# schemat.net
KiCad netlist of a schematic drawn in Altium Designer
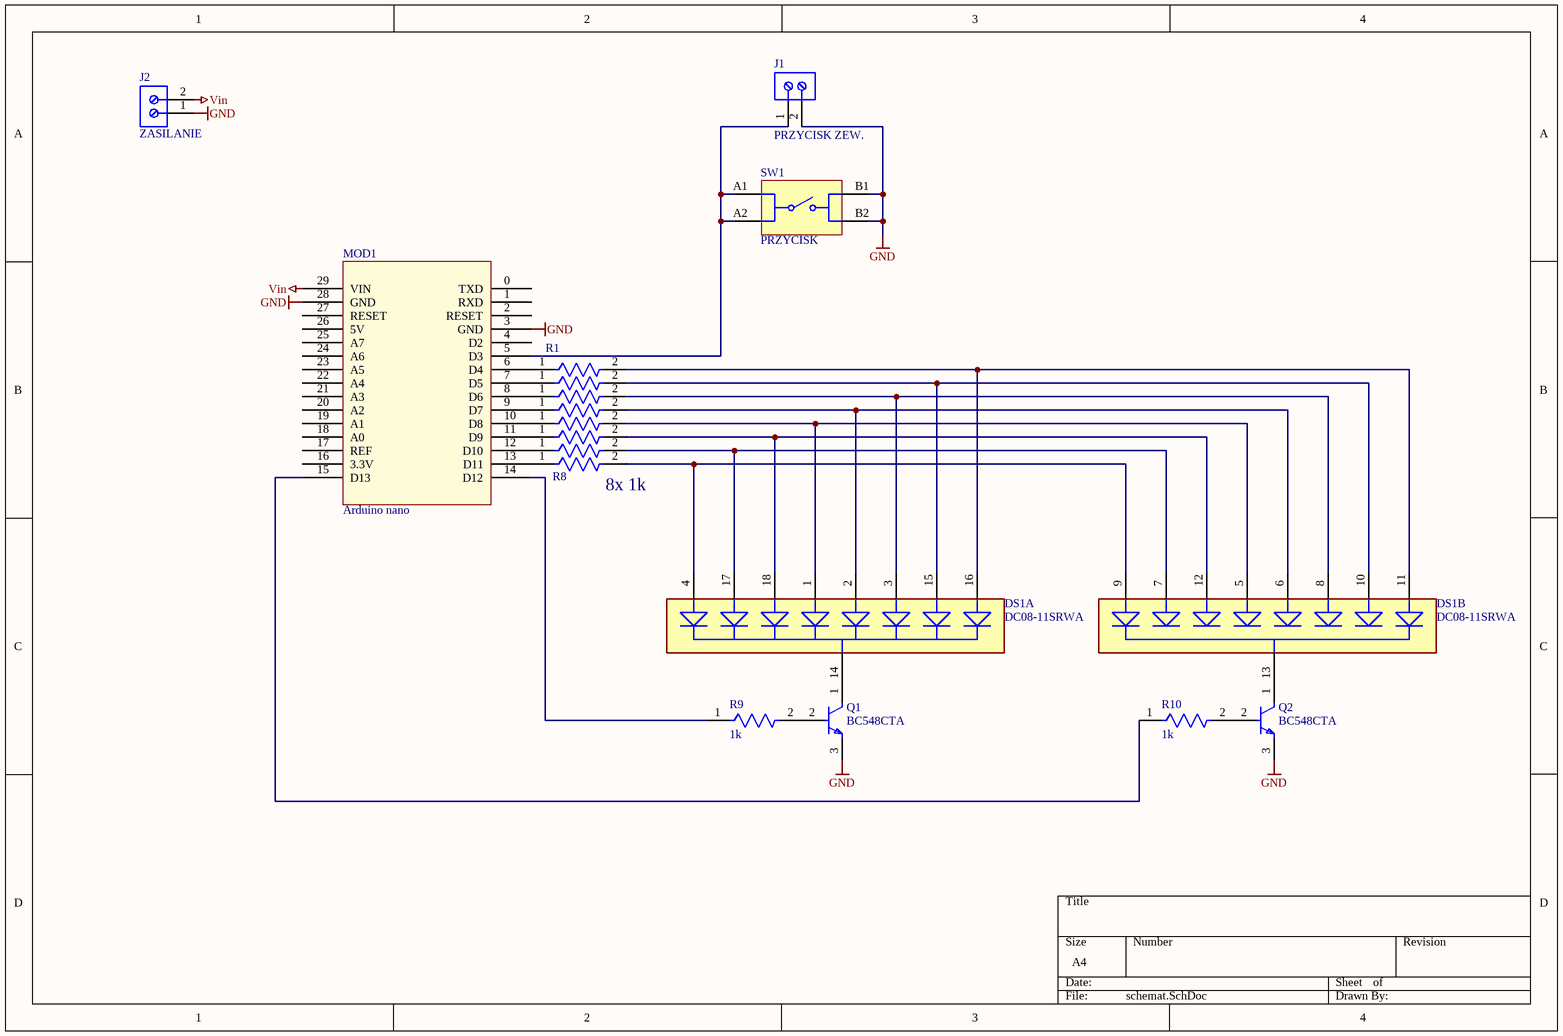
[diagram p0: schemat.SchDoc]

(export (version "E")
  (design (tool "Eeschema 10.0.6"))
  (components
    (comp (ref "DS1")
      (value "DC08-11SRWA")
      (footprint "FP-DC08-11SRWA-MFG")
      (description "DISPLAY 660NM RED 2DIG 0.8\" 7SEG")
      (fields
        (field (name "MANUFACTURER") "Kingbright")
        (field (name "OCTOPART") "https://octopart.com/dc08-11srwa-kingbright-55457135")
      )
      (libsource (lib "Altium Content Vault") (part "c040866fd5d19d735211b9114a29ce2"))
    )
    (comp (ref "J1")
      (value "PRZYCISK ZEW.")
      (footprint "691102710002")
      (fields (field (name "VOLTAGE") "300V"))
      (libsource (lib "Altium Content Vault") (part "TBL - 1R - 02P - Screw"))
    )
    (comp (ref "J2")
      (value "ZASILANIE")
      (footprint "691102710002")
      (fields (field (name "VOLTAGE") "300V"))
      (libsource (lib "Altium Content Vault") (part "TBL - 1R - 02P - Screw"))
    )
    (comp (ref "MOD1")
      (value "Arduino nano")
      (footprint "Arduino nano")
      (libsource (lib "schematic") (part "Arduino_nano"))
    )
    (comp (ref "Q1")
      (value "BC548CTA")
      (footprint "FP-135AR-MFG")
      (description "BC548CTA Small Signal Bipolar Transistor, 0.1A I(C), 30V V(BR)CEO, 1-Element, NPN, Silicon, TO-92")
      (libsource (lib "Altium Content Vault") (part "ddb5dc480c9317d3b8a15cf6cf16fd3"))
    )
    (comp (ref "Q2")
      (value "BC548CTA")
      (footprint "FP-135AR-MFG")
      (description "BC548CTA Small Signal Bipolar Transistor, 0.1A I(C), 30V V(BR)CEO, 1-Element, NPN, Silicon, TO-92")
      (libsource (lib "Altium Content Vault") (part "ddb5dc480c9317d3b8a15cf6cf16fd3"))
    )
    (comp (ref "R1")
      (value "1k")
      (footprint "FP-CF18-MFG")
      (description "RES 10K OHM 1/8W 5% CF AXIAL")
      (fields
        (field (name "MANUFACTURER PART NUMBER") "CF18JT10K0")
        (field (name "MANUFACTURER") "Stackpole Electronics")
      )
      (libsource (lib "Altium Content Vault") (part "1029c3af85768c4190bb7ad29bc67b5"))
    )
    (comp (ref "R2")
      (value "1k")
      (footprint "FP-CF18-MFG")
      (description "RES 10K OHM 1/8W 5% CF AXIAL")
      (fields
        (field (name "MANUFACTURER PART NUMBER") "CF18JT10K0")
        (field (name "MANUFACTURER") "Stackpole Electronics")
      )
      (libsource (lib "Altium Content Vault") (part "1029c3af85768c4190bb7ad29bc67b5"))
    )
    (comp (ref "R3")
      (value "1k")
      (footprint "FP-CF18-MFG")
      (description "RES 10K OHM 1/8W 5% CF AXIAL")
      (fields
        (field (name "MANUFACTURER PART NUMBER") "CF18JT10K0")
        (field (name "MANUFACTURER") "Stackpole Electronics")
      )
      (libsource (lib "Altium Content Vault") (part "1029c3af85768c4190bb7ad29bc67b5"))
    )
    (comp (ref "R4")
      (value "1k")
      (footprint "FP-CF18-MFG")
      (description "RES 10K OHM 1/8W 5% CF AXIAL")
      (fields
        (field (name "MANUFACTURER PART NUMBER") "CF18JT10K0")
        (field (name "MANUFACTURER") "Stackpole Electronics")
      )
      (libsource (lib "Altium Content Vault") (part "1029c3af85768c4190bb7ad29bc67b5"))
    )
    (comp (ref "R5")
      (value "1k")
      (footprint "FP-CF18-MFG")
      (description "RES 10K OHM 1/8W 5% CF AXIAL")
      (fields
        (field (name "MANUFACTURER PART NUMBER") "CF18JT10K0")
        (field (name "MANUFACTURER") "Stackpole Electronics")
      )
      (libsource (lib "Altium Content Vault") (part "1029c3af85768c4190bb7ad29bc67b5"))
    )
    (comp (ref "R6")
      (value "1k")
      (footprint "FP-CF18-MFG")
      (description "RES 10K OHM 1/8W 5% CF AXIAL")
      (fields
        (field (name "MANUFACTURER PART NUMBER") "CF18JT10K0")
        (field (name "MANUFACTURER") "Stackpole Electronics")
      )
      (libsource (lib "Altium Content Vault") (part "1029c3af85768c4190bb7ad29bc67b5"))
    )
    (comp (ref "R7")
      (value "1k")
      (footprint "FP-CF18-MFG")
      (description "RES 10K OHM 1/8W 5% CF AXIAL")
      (fields
        (field (name "MANUFACTURER PART NUMBER") "CF18JT10K0")
        (field (name "MANUFACTURER") "Stackpole Electronics")
      )
      (libsource (lib "Altium Content Vault") (part "1029c3af85768c4190bb7ad29bc67b5"))
    )
    (comp (ref "R8")
      (value "1k")
      (footprint "FP-CF18-MFG")
      (description "RES 10K OHM 1/8W 5% CF AXIAL")
      (fields
        (field (name "MANUFACTURER PART NUMBER") "CF18JT10K0")
        (field (name "MANUFACTURER") "Stackpole Electronics")
      )
      (libsource (lib "Altium Content Vault") (part "1029c3af85768c4190bb7ad29bc67b5"))
    )
    (comp (ref "R9")
      (value "1k")
      (footprint "FP-CF18-MFG")
      (description "RES 10K OHM 1/8W 5% CF AXIAL")
      (fields
        (field (name "MANUFACTURER PART NUMBER") "CF18JT10K0")
        (field (name "MANUFACTURER") "Stackpole Electronics")
      )
      (libsource (lib "Altium Content Vault") (part "1029c3af85768c4190bb7ad29bc67b5"))
    )
    (comp (ref "R10")
      (value "1k")
      (footprint "FP-CF18-MFG")
      (description "RES 10K OHM 1/8W 5% CF AXIAL")
      (fields
        (field (name "MANUFACTURER PART NUMBER") "CF18JT10K0")
        (field (name "MANUFACTURER") "Stackpole Electronics")
      )
      (libsource (lib "Altium Content Vault") (part "1029c3af85768c4190bb7ad29bc67b5"))
    )
    (comp (ref "SW1")
      (value "PRZYCISK")
      (footprint "4304x60437x6")
      (libsource (lib "Altium Content Vault") (part "SPST-NO_4P"))
    )
  )
  (nets
    (net (code "1") (name "GND") (class "Default")
      (node (ref "J1") (pin "2") (pinfunction "2_2") (pintype "passive"))
      (node (ref "J2") (pin "1") (pinfunction "1_1") (pintype "passive"))
      (node (ref "MOD1") (pin "28") (pinfunction "GND_28") (pintype "passive"))
      (node (ref "MOD1") (pin "3") (pinfunction "GND_3") (pintype "passive"))
      (node (ref "Q1") (pin "3") (pinfunction "E_3") (pintype "passive"))
      (node (ref "Q2") (pin "3") (pinfunction "E_3") (pintype "passive"))
      (node (ref "SW1") (pin "B1") (pinfunction "B1_B1") (pintype "passive"))
      (node (ref "SW1") (pin "B2") (pinfunction "B2_B2") (pintype "passive"))
    )
    (net (code "2") (name "Net-(DS1A-Anode_Dp1_Dig1)") (class "Default")
      (node (ref "DS1") (pin "4") (pinfunction "Anode_Dp1_Dig1_4") (pintype "passive"))
      (node (ref "DS1") (pin "9") (pinfunction "Anode_Dp2_Dig2_9") (pintype "passive"))
      (node (ref "R8") (pin "2") (pinfunction "2_2") (pintype "passive"))
    )
    (net (code "3") (name "Net-(DS1A-Anode_a_Dig1)") (class "Default")
      (node (ref "DS1") (pin "11") (pinfunction "Anode_a_Dig2_11") (pintype "passive"))
      (node (ref "DS1") (pin "16") (pinfunction "Anode_a_Dig1_16") (pintype "passive"))
      (node (ref "R1") (pin "2") (pinfunction "2_2") (pintype "passive"))
    )
    (net (code "4") (name "Net-(DS1A-Anode_b_Dig1)") (class "Default")
      (node (ref "DS1") (pin "10") (pinfunction "Anode_b_Dig2_10") (pintype "passive"))
      (node (ref "DS1") (pin "15") (pinfunction "Anode_b_Dig1_15") (pintype "passive"))
      (node (ref "R2") (pin "2") (pinfunction "2_2") (pintype "passive"))
    )
    (net (code "5") (name "Net-(DS1A-Anode_c_Dig1)") (class "Default")
      (node (ref "DS1") (pin "3") (pinfunction "Anode_c_Dig1_3") (pintype "passive"))
      (node (ref "DS1") (pin "8") (pinfunction "Anode_c_Dig2_8") (pintype "passive"))
      (node (ref "R3") (pin "2") (pinfunction "2_2") (pintype "passive"))
    )
    (net (code "6") (name "Net-(DS1A-Anode_d_Dig1)") (class "Default")
      (node (ref "DS1") (pin "2") (pinfunction "Anode_d_Dig1_2") (pintype "passive"))
      (node (ref "DS1") (pin "6") (pinfunction "Anode_d_Dig2_6") (pintype "passive"))
      (node (ref "R4") (pin "2") (pinfunction "2_2") (pintype "passive"))
    )
    (net (code "7") (name "Net-(DS1A-Anode_e_Dig1)") (class "Default")
      (node (ref "DS1") (pin "1") (pinfunction "Anode_e_Dig1_1") (pintype "passive"))
      (node (ref "DS1") (pin "5") (pinfunction "Anode_e_Dig2_5") (pintype "passive"))
      (node (ref "R5") (pin "2") (pinfunction "2_2") (pintype "passive"))
    )
    (net (code "8") (name "Net-(DS1A-Anode_f_Dig1)") (class "Default")
      (node (ref "DS1") (pin "12") (pinfunction "Anode_f_Dig2_12") (pintype "passive"))
      (node (ref "DS1") (pin "18") (pinfunction "Anode_f_Dig1_18") (pintype "passive"))
      (node (ref "R6") (pin "2") (pinfunction "2_2") (pintype "passive"))
    )
    (net (code "9") (name "Net-(DS1A-Anode_g_Dig1)") (class "Default")
      (node (ref "DS1") (pin "17") (pinfunction "Anode_g_Dig1_17") (pintype "passive"))
      (node (ref "DS1") (pin "7") (pinfunction "Anode_g_Dig2_7") (pintype "passive"))
      (node (ref "R7") (pin "2") (pinfunction "2_2") (pintype "passive"))
    )
    (net (code "10") (name "Net-(DS1A-Common_Cathode_Dig1)") (class "Default")
      (node (ref "DS1") (pin "14") (pinfunction "Common_Cathode_Dig1_14") (pintype "passive"))
      (node (ref "Q1") (pin "1") (pinfunction "C_1") (pintype "passive"))
    )
    (net (code "11") (name "Net-(DS1B-Common_Cathode_Dig2)") (class "Default")
      (node (ref "DS1") (pin "13") (pinfunction "Common_Cathode_Dig2_13") (pintype "passive"))
      (node (ref "Q2") (pin "1") (pinfunction "C_1") (pintype "passive"))
    )
    (net (code "12") (name "Net-(MOD1-D3)") (class "Default")
      (node (ref "J1") (pin "1") (pinfunction "1_1") (pintype "passive"))
      (node (ref "MOD1") (pin "5") (pinfunction "D3_5") (pintype "passive"))
      (node (ref "SW1") (pin "A1") (pinfunction "A1_A1") (pintype "passive"))
      (node (ref "SW1") (pin "A2") (pinfunction "A2_A2") (pintype "passive"))
    )
    (net (code "13") (name "Net-(MOD1-D4)") (class "Default")
      (node (ref "MOD1") (pin "6") (pinfunction "D4_6") (pintype "passive"))
      (node (ref "R1") (pin "1") (pinfunction "1_1") (pintype "passive"))
    )
    (net (code "14") (name "Net-(MOD1-D5)") (class "Default")
      (node (ref "MOD1") (pin "7") (pinfunction "D5_7") (pintype "passive"))
      (node (ref "R2") (pin "1") (pinfunction "1_1") (pintype "passive"))
    )
    (net (code "15") (name "Net-(MOD1-D6)") (class "Default")
      (node (ref "MOD1") (pin "8") (pinfunction "D6_8") (pintype "passive"))
      (node (ref "R3") (pin "1") (pinfunction "1_1") (pintype "passive"))
    )
    (net (code "16") (name "Net-(MOD1-D7)") (class "Default")
      (node (ref "MOD1") (pin "9") (pinfunction "D7_9") (pintype "passive"))
      (node (ref "R4") (pin "1") (pinfunction "1_1") (pintype "passive"))
    )
    (net (code "17") (name "Net-(MOD1-D8)") (class "Default")
      (node (ref "MOD1") (pin "10") (pinfunction "D8_10") (pintype "passive"))
      (node (ref "R5") (pin "1") (pinfunction "1_1") (pintype "passive"))
    )
    (net (code "18") (name "Net-(MOD1-D9)") (class "Default")
      (node (ref "MOD1") (pin "11") (pinfunction "D9_11") (pintype "passive"))
      (node (ref "R6") (pin "1") (pinfunction "1_1") (pintype "passive"))
    )
    (net (code "19") (name "Net-(MOD1-D10)") (class "Default")
      (node (ref "MOD1") (pin "12") (pinfunction "D10_12") (pintype "passive"))
      (node (ref "R7") (pin "1") (pinfunction "1_1") (pintype "passive"))
    )
    (net (code "20") (name "Net-(MOD1-D11)") (class "Default")
      (node (ref "MOD1") (pin "13") (pinfunction "D11_13") (pintype "passive"))
      (node (ref "R8") (pin "1") (pinfunction "1_1") (pintype "passive"))
    )
    (net (code "21") (name "Net-(MOD1-D12)") (class "Default")
      (node (ref "MOD1") (pin "14") (pinfunction "D12_14") (pintype "passive"))
      (node (ref "R9") (pin "1") (pinfunction "1_1") (pintype "passive"))
    )
    (net (code "22") (name "Net-(MOD1-D13)") (class "Default")
      (node (ref "MOD1") (pin "15") (pinfunction "D13_15") (pintype "passive"))
      (node (ref "R10") (pin "1") (pinfunction "1_1") (pintype "passive"))
    )
    (net (code "23") (name "Net-(Q1-B)") (class "Default")
      (node (ref "Q1") (pin "2") (pinfunction "B_2") (pintype "passive"))
      (node (ref "R9") (pin "2") (pinfunction "2_2") (pintype "passive"))
    )
    (net (code "24") (name "Net-(Q2-B)") (class "Default")
      (node (ref "Q2") (pin "2") (pinfunction "B_2") (pintype "passive"))
      (node (ref "R10") (pin "2") (pinfunction "2_2") (pintype "passive"))
    )
    (net (code "25") (name "Vin") (class "Default")
      (node (ref "J2") (pin "2") (pinfunction "2_2") (pintype "passive"))
      (node (ref "MOD1") (pin "29") (pinfunction "VIN_29") (pintype "passive"))
    )
    (net (code "26") (name "unconnected-(MOD1-3.3V-Pad16)") (class "Default")
      (node (ref "MOD1") (pin "16") (pinfunction "3.3V_16") (pintype "passive"))
    )
    (net (code "27") (name "unconnected-(MOD1-5V-Pad26)") (class "Default")
      (node (ref "MOD1") (pin "26") (pinfunction "5V_26") (pintype "passive"))
    )
    (net (code "28") (name "unconnected-(MOD1-A0-Pad18)") (class "Default")
      (node (ref "MOD1") (pin "18") (pinfunction "A0_18") (pintype "passive"))
    )
    (net (code "29") (name "unconnected-(MOD1-A1-Pad19)") (class "Default")
      (node (ref "MOD1") (pin "19") (pinfunction "A1_19") (pintype "passive"))
    )
    (net (code "30") (name "unconnected-(MOD1-A2-Pad20)") (class "Default")
      (node (ref "MOD1") (pin "20") (pinfunction "A2_20") (pintype "passive"))
    )
    (net (code "31") (name "unconnected-(MOD1-A3-Pad21)") (class "Default")
      (node (ref "MOD1") (pin "21") (pinfunction "A3_21") (pintype "passive"))
    )
    (net (code "32") (name "unconnected-(MOD1-A4-Pad22)") (class "Default")
      (node (ref "MOD1") (pin "22") (pinfunction "A4_22") (pintype "passive"))
    )
    (net (code "33") (name "unconnected-(MOD1-A5-Pad23)") (class "Default")
      (node (ref "MOD1") (pin "23") (pinfunction "A5_23") (pintype "passive"))
    )
    (net (code "34") (name "unconnected-(MOD1-A6-Pad24)") (class "Default")
      (node (ref "MOD1") (pin "24") (pinfunction "A6_24") (pintype "passive"))
    )
    (net (code "35") (name "unconnected-(MOD1-A7-Pad25)") (class "Default")
      (node (ref "MOD1") (pin "25") (pinfunction "A7_25") (pintype "passive"))
    )
    (net (code "36") (name "unconnected-(MOD1-D2-Pad4)") (class "Default")
      (node (ref "MOD1") (pin "4") (pinfunction "D2_4") (pintype "passive"))
    )
    (net (code "37") (name "unconnected-(MOD1-REF-Pad17)") (class "Default")
      (node (ref "MOD1") (pin "17") (pinfunction "REF_17") (pintype "passive"))
    )
    (net (code "38") (name "unconnected-(MOD1-RESET-Pad2)") (class "Default")
      (node (ref "MOD1") (pin "2") (pinfunction "RESET_2") (pintype "passive"))
    )
    (net (code "39") (name "unconnected-(MOD1-RESET-Pad27)") (class "Default")
      (node (ref "MOD1") (pin "27") (pinfunction "RESET_27") (pintype "passive"))
    )
    (net (code "40") (name "unconnected-(MOD1-RXD-Pad1)") (class "Default")
      (node (ref "MOD1") (pin "1") (pinfunction "RXD_1") (pintype "passive"))
    )
    (net (code "41") (name "unconnected-(MOD1-TXD-Pad0)") (class "Default")
      (node (ref "MOD1") (pin "0") (pinfunction "TXD_0") (pintype "passive"))
    )
  )
)
